# M2.net
KiCad netlist of a schematic drawn in Altium Designer
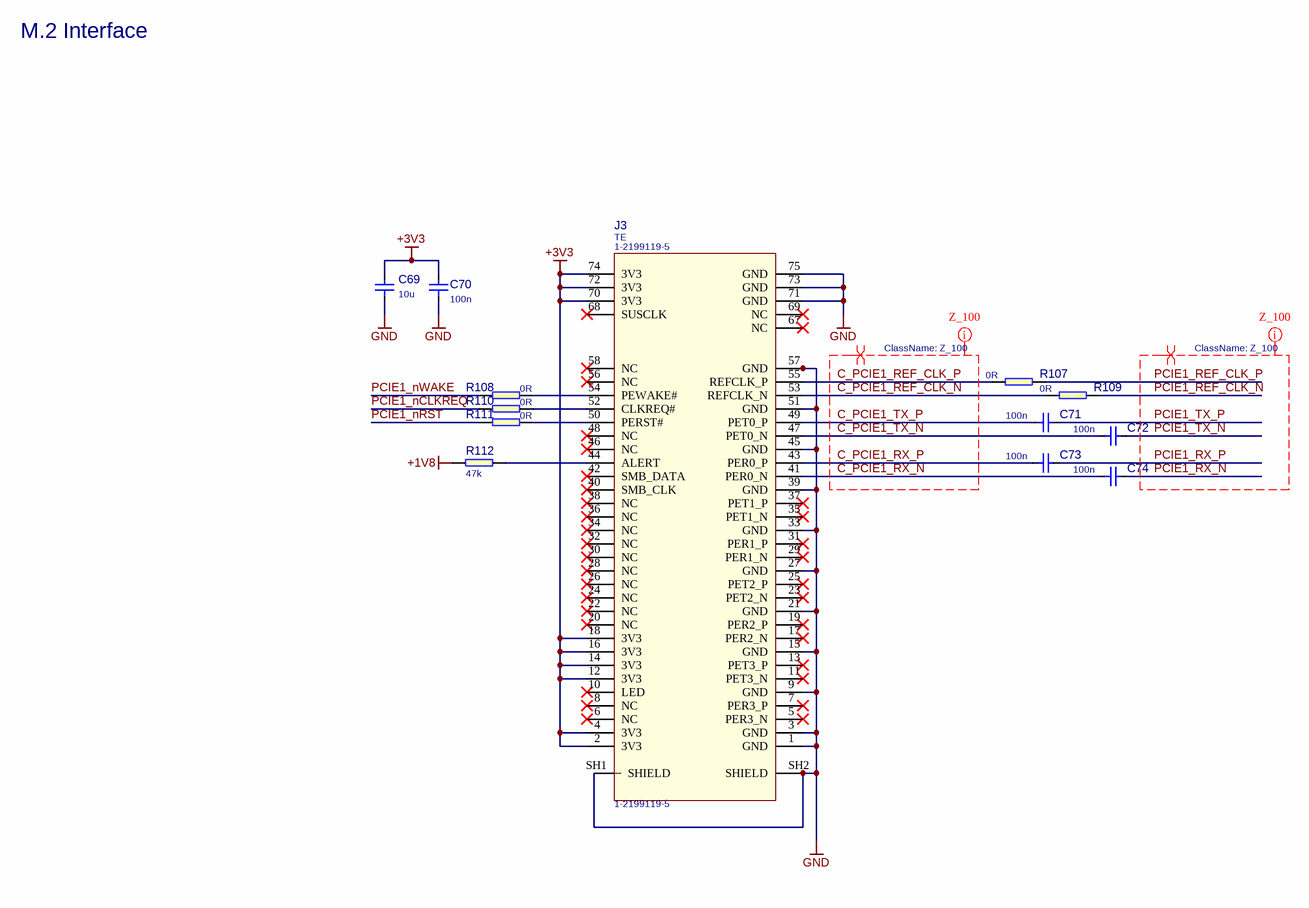
[diagram p0: M2.SchDoc]

(export (version "E")
  (design (tool "Eeschema 10.0.6"))
  (components
    (comp (ref "C69")
      (value "10u")
      (footprint "0805")
      (description "MLCC SMT Capacitor 10uF 0805")
      (fields (field (name "PARTNUMBER") "C_10u_0805"))
      (libsource (lib "altium-import") (part "root_1_C_"))
    )
    (comp (ref "C70")
      (value "100n")
      (footprint "C_0402")
      (description "MLCC SMT Capacitor 100nF 0402")
      (fields (field (name "PARTNUMBER") "C_100n_0402"))
      (libsource (lib "altium-import") (part "root_1_C_"))
    )
    (comp (ref "C71")
      (value "100n")
      (footprint "C_0402")
      (description "MLCC SMT Capacitor 100nF 0402")
      (fields (field (name "PARTNUMBER") "C_100n_0402"))
      (libsource (lib "altium-import") (part "root_0_C_"))
    )
    (comp (ref "C72")
      (value "100n")
      (footprint "C_0402")
      (description "MLCC SMT Capacitor 100nF 0402")
      (fields (field (name "PARTNUMBER") "C_100n_0402"))
      (libsource (lib "altium-import") (part "root_0_C_"))
    )
    (comp (ref "C73")
      (value "100n")
      (footprint "C_0402")
      (description "MLCC SMT Capacitor 100nF 0402")
      (fields (field (name "PARTNUMBER") "C_100n_0402"))
      (libsource (lib "altium-import") (part "root_0_C_"))
    )
    (comp (ref "C74")
      (value "100n")
      (footprint "C_0402")
      (description "MLCC SMT Capacitor 100nF 0402")
      (fields (field (name "PARTNUMBER") "C_100n_0402"))
      (libsource (lib "altium-import") (part "root_0_C_"))
    )
    (comp (ref "J3")
      (value "1-2199119-5")
      (footprint "1-2199119-5")
      (description "CONN FEMALE 67POS 0.020 GOLD")
      (fields (field (name "PARTNUMBER") "1-2199119-5") (field (name "MANUFACTURER") "TE"))
      (libsource (lib "altium-import") (part "root_0_1-2199119-5_"))
    )
    (comp (ref "R107")
      (value "0R")
      (footprint "0402")
      (description "SMT Resistor 0402")
      (fields (field (name "PARTNUMBER") "R_0R_0402"))
      (libsource (lib "altium-import") (part "root_0_R_"))
    )
    (comp (ref "R108")
      (value "0R")
      (footprint "0402")
      (description "SMT Resistor 0402")
      (fields (field (name "PARTNUMBER") "R_0R_0402"))
      (libsource (lib "altium-import") (part "root_0_R_"))
    )
    (comp (ref "R109")
      (value "0R")
      (footprint "0402")
      (description "SMT Resistor 0402")
      (fields (field (name "PARTNUMBER") "R_0R_0402"))
      (libsource (lib "altium-import") (part "root_0_R_"))
    )
    (comp (ref "R110")
      (value "0R")
      (footprint "0402")
      (description "SMT Resistor 0402")
      (fields (field (name "PARTNUMBER") "R_0R_0402"))
      (libsource (lib "altium-import") (part "root_0_R_"))
    )
    (comp (ref "R111")
      (value "0R")
      (footprint "0402")
      (description "SMT Resistor 0402")
      (fields (field (name "PARTNUMBER") "R_0R_0402"))
      (libsource (lib "altium-import") (part "root_0_R_"))
    )
    (comp (ref "R112")
      (value "47k")
      (footprint "0402")
      (description "SMT Resistor 0402")
      (fields (field (name "PARTNUMBER") "R_47k_0402"))
      (libsource (lib "altium-import") (part "root_2_R_"))
    )
  )
  (nets
    (net (code "1") (name "+1V8") (class "Default") (node (ref "R112") (pin "2") (pintype "passive")))
    (net (code "2") (name "+3V3") (class "Default")
      (node (ref "C69") (pin "2") (pinfunction "2_2") (pintype "passive"))
      (node (ref "C70") (pin "2") (pinfunction "2_2") (pintype "passive"))
      (node (ref "J3") (pin "12") (pinfunction "3V3_12") (pintype "passive"))
      (node (ref "J3") (pin "14") (pinfunction "3V3_14") (pintype "passive"))
      (node (ref "J3") (pin "16") (pinfunction "3V3_16") (pintype "passive"))
      (node (ref "J3") (pin "18") (pinfunction "3V3_18") (pintype "passive"))
      (node (ref "J3") (pin "2") (pinfunction "3V3_2") (pintype "passive"))
      (node (ref "J3") (pin "4") (pinfunction "3V3_4") (pintype "passive"))
      (node (ref "J3") (pin "70") (pinfunction "3V3_70") (pintype "passive"))
      (node (ref "J3") (pin "72") (pinfunction "3V3_72") (pintype "passive"))
      (node (ref "J3") (pin "74") (pinfunction "3V3_74") (pintype "passive"))
    )
    (net (code "3") (name "/C_PCIE1_REF_CLK_N") (class "Default")
      (node (ref "J3") (pin "53") (pinfunction "REFCLK_N_53") (pintype "passive"))
      (node (ref "R109") (pin "1") (pintype "passive"))
    )
    (net (code "4") (name "/C_PCIE1_REF_CLK_P") (class "Default")
      (node (ref "J3") (pin "55") (pinfunction "REFCLK_P_55") (pintype "passive"))
      (node (ref "R107") (pin "1") (pintype "passive"))
    )
    (net (code "5") (name "/C_PCIE1_RX_N") (class "Default")
      (node (ref "C74") (pin "1") (pinfunction "1_1") (pintype "passive"))
      (node (ref "J3") (pin "41") (pinfunction "PER0_N_41") (pintype "passive"))
    )
    (net (code "6") (name "/C_PCIE1_RX_P") (class "Default")
      (node (ref "C73") (pin "1") (pinfunction "1_1") (pintype "passive"))
      (node (ref "J3") (pin "43") (pinfunction "PER0_P_43") (pintype "passive"))
    )
    (net (code "7") (name "/C_PCIE1_TX_N") (class "Default")
      (node (ref "C72") (pin "1") (pinfunction "1_1") (pintype "passive"))
      (node (ref "J3") (pin "47") (pinfunction "PET0_N_47") (pintype "passive"))
    )
    (net (code "8") (name "/C_PCIE1_TX_P") (class "Default")
      (node (ref "C71") (pin "1") (pinfunction "1_1") (pintype "passive"))
      (node (ref "J3") (pin "49") (pinfunction "PET0_P_49") (pintype "passive"))
    )
    (net (code "9") (name "/PCIE1_REF_CLK_N") (class "Default")
      (node (ref "R109") (pin "2") (pintype "passive"))
    )
    (net (code "10") (name "/PCIE1_REF_CLK_P") (class "Default")
      (node (ref "R107") (pin "2") (pintype "passive"))
    )
    (net (code "11") (name "/PCIE1_RX_N") (class "Default")
      (node (ref "C74") (pin "2") (pinfunction "2_2") (pintype "passive"))
    )
    (net (code "12") (name "/PCIE1_RX_P") (class "Default")
      (node (ref "C73") (pin "2") (pinfunction "2_2") (pintype "passive"))
    )
    (net (code "13") (name "/PCIE1_TX_N") (class "Default")
      (node (ref "C72") (pin "2") (pinfunction "2_2") (pintype "passive"))
    )
    (net (code "14") (name "/PCIE1_TX_P") (class "Default")
      (node (ref "C71") (pin "2") (pinfunction "2_2") (pintype "passive"))
    )
    (net (code "15") (name "/PCIE1_nCLKREQ") (class "Default")
      (node (ref "R110") (pin "1") (pintype "passive"))
    )
    (net (code "16") (name "/PCIE1_nRST") (class "Default") (node (ref "R111") (pin "1") (pintype "passive")))
    (net (code "17") (name "/PCIE1_nWAKE") (class "Default")
      (node (ref "R108") (pin "1") (pintype "passive"))
    )
    (net (code "18") (name "GND") (class "Default")
      (node (ref "C69") (pin "1") (pinfunction "1_1") (pintype "passive"))
      (node (ref "C70") (pin "1") (pinfunction "1_1") (pintype "passive"))
      (node (ref "J3") (pin "1") (pinfunction "GND_1") (pintype "passive"))
      (node (ref "J3") (pin "15") (pinfunction "GND_15") (pintype "passive"))
      (node (ref "J3") (pin "21") (pinfunction "GND_21") (pintype "passive"))
      (node (ref "J3") (pin "27") (pinfunction "GND_27") (pintype "passive"))
      (node (ref "J3") (pin "3") (pinfunction "GND_3") (pintype "passive"))
      (node (ref "J3") (pin "33") (pinfunction "GND_33") (pintype "passive"))
      (node (ref "J3") (pin "39") (pinfunction "GND_39") (pintype "passive"))
      (node (ref "J3") (pin "45") (pinfunction "GND_45") (pintype "passive"))
      (node (ref "J3") (pin "51") (pinfunction "GND_51") (pintype "passive"))
      (node (ref "J3") (pin "57") (pinfunction "GND_57") (pintype "passive"))
      (node (ref "J3") (pin "71") (pinfunction "GND_71") (pintype "passive"))
      (node (ref "J3") (pin "73") (pinfunction "GND_73") (pintype "passive"))
      (node (ref "J3") (pin "75") (pinfunction "GND_75") (pintype "passive"))
      (node (ref "J3") (pin "9") (pinfunction "GND_9") (pintype "passive"))
      (node (ref "J3") (pin "SH1") (pinfunction "SHIELD_SH1") (pintype "passive"))
      (node (ref "J3") (pin "SH2") (pinfunction "SHIELD_SH2") (pintype "passive"))
    )
    (net (code "19") (name "Net-(J3-ALERT)") (class "Default")
      (node (ref "J3") (pin "44") (pinfunction "ALERT_44") (pintype "passive"))
      (node (ref "R112") (pin "1") (pintype "passive"))
    )
    (net (code "20") (name "Net-(J3-CLKREQ#)") (class "Default")
      (node (ref "J3") (pin "52") (pinfunction "CLKREQ#_52") (pintype "passive"))
      (node (ref "R110") (pin "2") (pintype "passive"))
    )
    (net (code "21") (name "Net-(J3-PERST#)") (class "Default")
      (node (ref "J3") (pin "50") (pinfunction "PERST#_50") (pintype "passive"))
      (node (ref "R111") (pin "2") (pintype "passive"))
    )
    (net (code "22") (name "Net-(J3-PEWAKE#)") (class "Default")
      (node (ref "J3") (pin "54") (pinfunction "PEWAKE#_54") (pintype "passive"))
      (node (ref "R108") (pin "2") (pintype "passive"))
    )
    (net (code "23") (name "unconnected-(J3-LED-Pad10)") (class "Default")
      (node (ref "J3") (pin "10") (pinfunction "LED_10") (pintype "passive+no_connect"))
    )
    (net (code "24") (name "unconnected-(J3-NC-Pad6)") (class "Default")
      (node (ref "J3") (pin "6") (pinfunction "NC_6") (pintype "passive+no_connect"))
    )
    (net (code "25") (name "unconnected-(J3-NC-Pad8)") (class "Default")
      (node (ref "J3") (pin "8") (pinfunction "NC_8") (pintype "passive+no_connect"))
    )
    (net (code "26") (name "unconnected-(J3-NC-Pad20)") (class "Default")
      (node (ref "J3") (pin "20") (pinfunction "NC_20") (pintype "passive+no_connect"))
    )
    (net (code "27") (name "unconnected-(J3-NC-Pad22)") (class "Default")
      (node (ref "J3") (pin "22") (pinfunction "NC_22") (pintype "passive+no_connect"))
    )
    (net (code "28") (name "unconnected-(J3-NC-Pad24)") (class "Default")
      (node (ref "J3") (pin "24") (pinfunction "NC_24") (pintype "passive+no_connect"))
    )
    (net (code "29") (name "unconnected-(J3-NC-Pad26)") (class "Default")
      (node (ref "J3") (pin "26") (pinfunction "NC_26") (pintype "passive+no_connect"))
    )
    (net (code "30") (name "unconnected-(J3-NC-Pad28)") (class "Default")
      (node (ref "J3") (pin "28") (pinfunction "NC_28") (pintype "passive+no_connect"))
    )
    (net (code "31") (name "unconnected-(J3-NC-Pad30)") (class "Default")
      (node (ref "J3") (pin "30") (pinfunction "NC_30") (pintype "passive+no_connect"))
    )
    (net (code "32") (name "unconnected-(J3-NC-Pad32)") (class "Default")
      (node (ref "J3") (pin "32") (pinfunction "NC_32") (pintype "passive+no_connect"))
    )
    (net (code "33") (name "unconnected-(J3-NC-Pad34)") (class "Default")
      (node (ref "J3") (pin "34") (pinfunction "NC_34") (pintype "passive+no_connect"))
    )
    (net (code "34") (name "unconnected-(J3-NC-Pad36)") (class "Default")
      (node (ref "J3") (pin "36") (pinfunction "NC_36") (pintype "passive+no_connect"))
    )
    (net (code "35") (name "unconnected-(J3-NC-Pad38)") (class "Default")
      (node (ref "J3") (pin "38") (pinfunction "NC_38") (pintype "passive+no_connect"))
    )
    (net (code "36") (name "unconnected-(J3-NC-Pad46)") (class "Default")
      (node (ref "J3") (pin "46") (pinfunction "NC_46") (pintype "passive+no_connect"))
    )
    (net (code "37") (name "unconnected-(J3-NC-Pad48)") (class "Default")
      (node (ref "J3") (pin "48") (pinfunction "NC_48") (pintype "passive+no_connect"))
    )
    (net (code "38") (name "unconnected-(J3-NC-Pad56)") (class "Default")
      (node (ref "J3") (pin "56") (pinfunction "NC_56") (pintype "passive+no_connect"))
    )
    (net (code "39") (name "unconnected-(J3-NC-Pad58)") (class "Default")
      (node (ref "J3") (pin "58") (pinfunction "NC_58") (pintype "passive+no_connect"))
    )
    (net (code "40") (name "unconnected-(J3-NC-Pad67)") (class "Default")
      (node (ref "J3") (pin "67") (pinfunction "NC_67") (pintype "passive+no_connect"))
    )
    (net (code "41") (name "unconnected-(J3-NC-Pad69)") (class "Default")
      (node (ref "J3") (pin "69") (pinfunction "NC_69") (pintype "passive+no_connect"))
    )
    (net (code "42") (name "unconnected-(J3-PER1_N-Pad29)") (class "Default")
      (node (ref "J3") (pin "29") (pinfunction "PER1_N_29") (pintype "passive+no_connect"))
    )
    (net (code "43") (name "unconnected-(J3-PER1_P-Pad31)") (class "Default")
      (node (ref "J3") (pin "31") (pinfunction "PER1_P_31") (pintype "passive+no_connect"))
    )
    (net (code "44") (name "unconnected-(J3-PER2_N-Pad17)") (class "Default")
      (node (ref "J3") (pin "17") (pinfunction "PER2_N_17") (pintype "passive+no_connect"))
    )
    (net (code "45") (name "unconnected-(J3-PER2_P-Pad19)") (class "Default")
      (node (ref "J3") (pin "19") (pinfunction "PER2_P_19") (pintype "passive+no_connect"))
    )
    (net (code "46") (name "unconnected-(J3-PER3_N-Pad5)") (class "Default")
      (node (ref "J3") (pin "5") (pinfunction "PER3_N_5") (pintype "passive+no_connect"))
    )
    (net (code "47") (name "unconnected-(J3-PER3_P-Pad7)") (class "Default")
      (node (ref "J3") (pin "7") (pinfunction "PER3_P_7") (pintype "passive+no_connect"))
    )
    (net (code "48") (name "unconnected-(J3-PET1_N-Pad35)") (class "Default")
      (node (ref "J3") (pin "35") (pinfunction "PET1_N_35") (pintype "passive+no_connect"))
    )
    (net (code "49") (name "unconnected-(J3-PET1_P-Pad37)") (class "Default")
      (node (ref "J3") (pin "37") (pinfunction "PET1_P_37") (pintype "passive+no_connect"))
    )
    (net (code "50") (name "unconnected-(J3-PET2_N-Pad23)") (class "Default")
      (node (ref "J3") (pin "23") (pinfunction "PET2_N_23") (pintype "passive+no_connect"))
    )
    (net (code "51") (name "unconnected-(J3-PET2_P-Pad25)") (class "Default")
      (node (ref "J3") (pin "25") (pinfunction "PET2_P_25") (pintype "passive+no_connect"))
    )
    (net (code "52") (name "unconnected-(J3-PET3_N-Pad11)") (class "Default")
      (node (ref "J3") (pin "11") (pinfunction "PET3_N_11") (pintype "passive+no_connect"))
    )
    (net (code "53") (name "unconnected-(J3-PET3_P-Pad13)") (class "Default")
      (node (ref "J3") (pin "13") (pinfunction "PET3_P_13") (pintype "passive+no_connect"))
    )
    (net (code "54") (name "unconnected-(J3-SMB_CLK-Pad40)") (class "Default")
      (node (ref "J3") (pin "40") (pinfunction "SMB_CLK_40") (pintype "passive+no_connect"))
    )
    (net (code "55") (name "unconnected-(J3-SMB_DATA-Pad42)") (class "Default")
      (node (ref "J3") (pin "42") (pinfunction "SMB_DATA_42") (pintype "passive+no_connect"))
    )
    (net (code "56") (name "unconnected-(J3-SUSCLK-Pad68)") (class "Default")
      (node (ref "J3") (pin "68") (pinfunction "SUSCLK_68") (pintype "passive+no_connect"))
    )
  )
)
